# AcceLog_v00.net
KiCad netlist of a schematic drawn in EAGLE
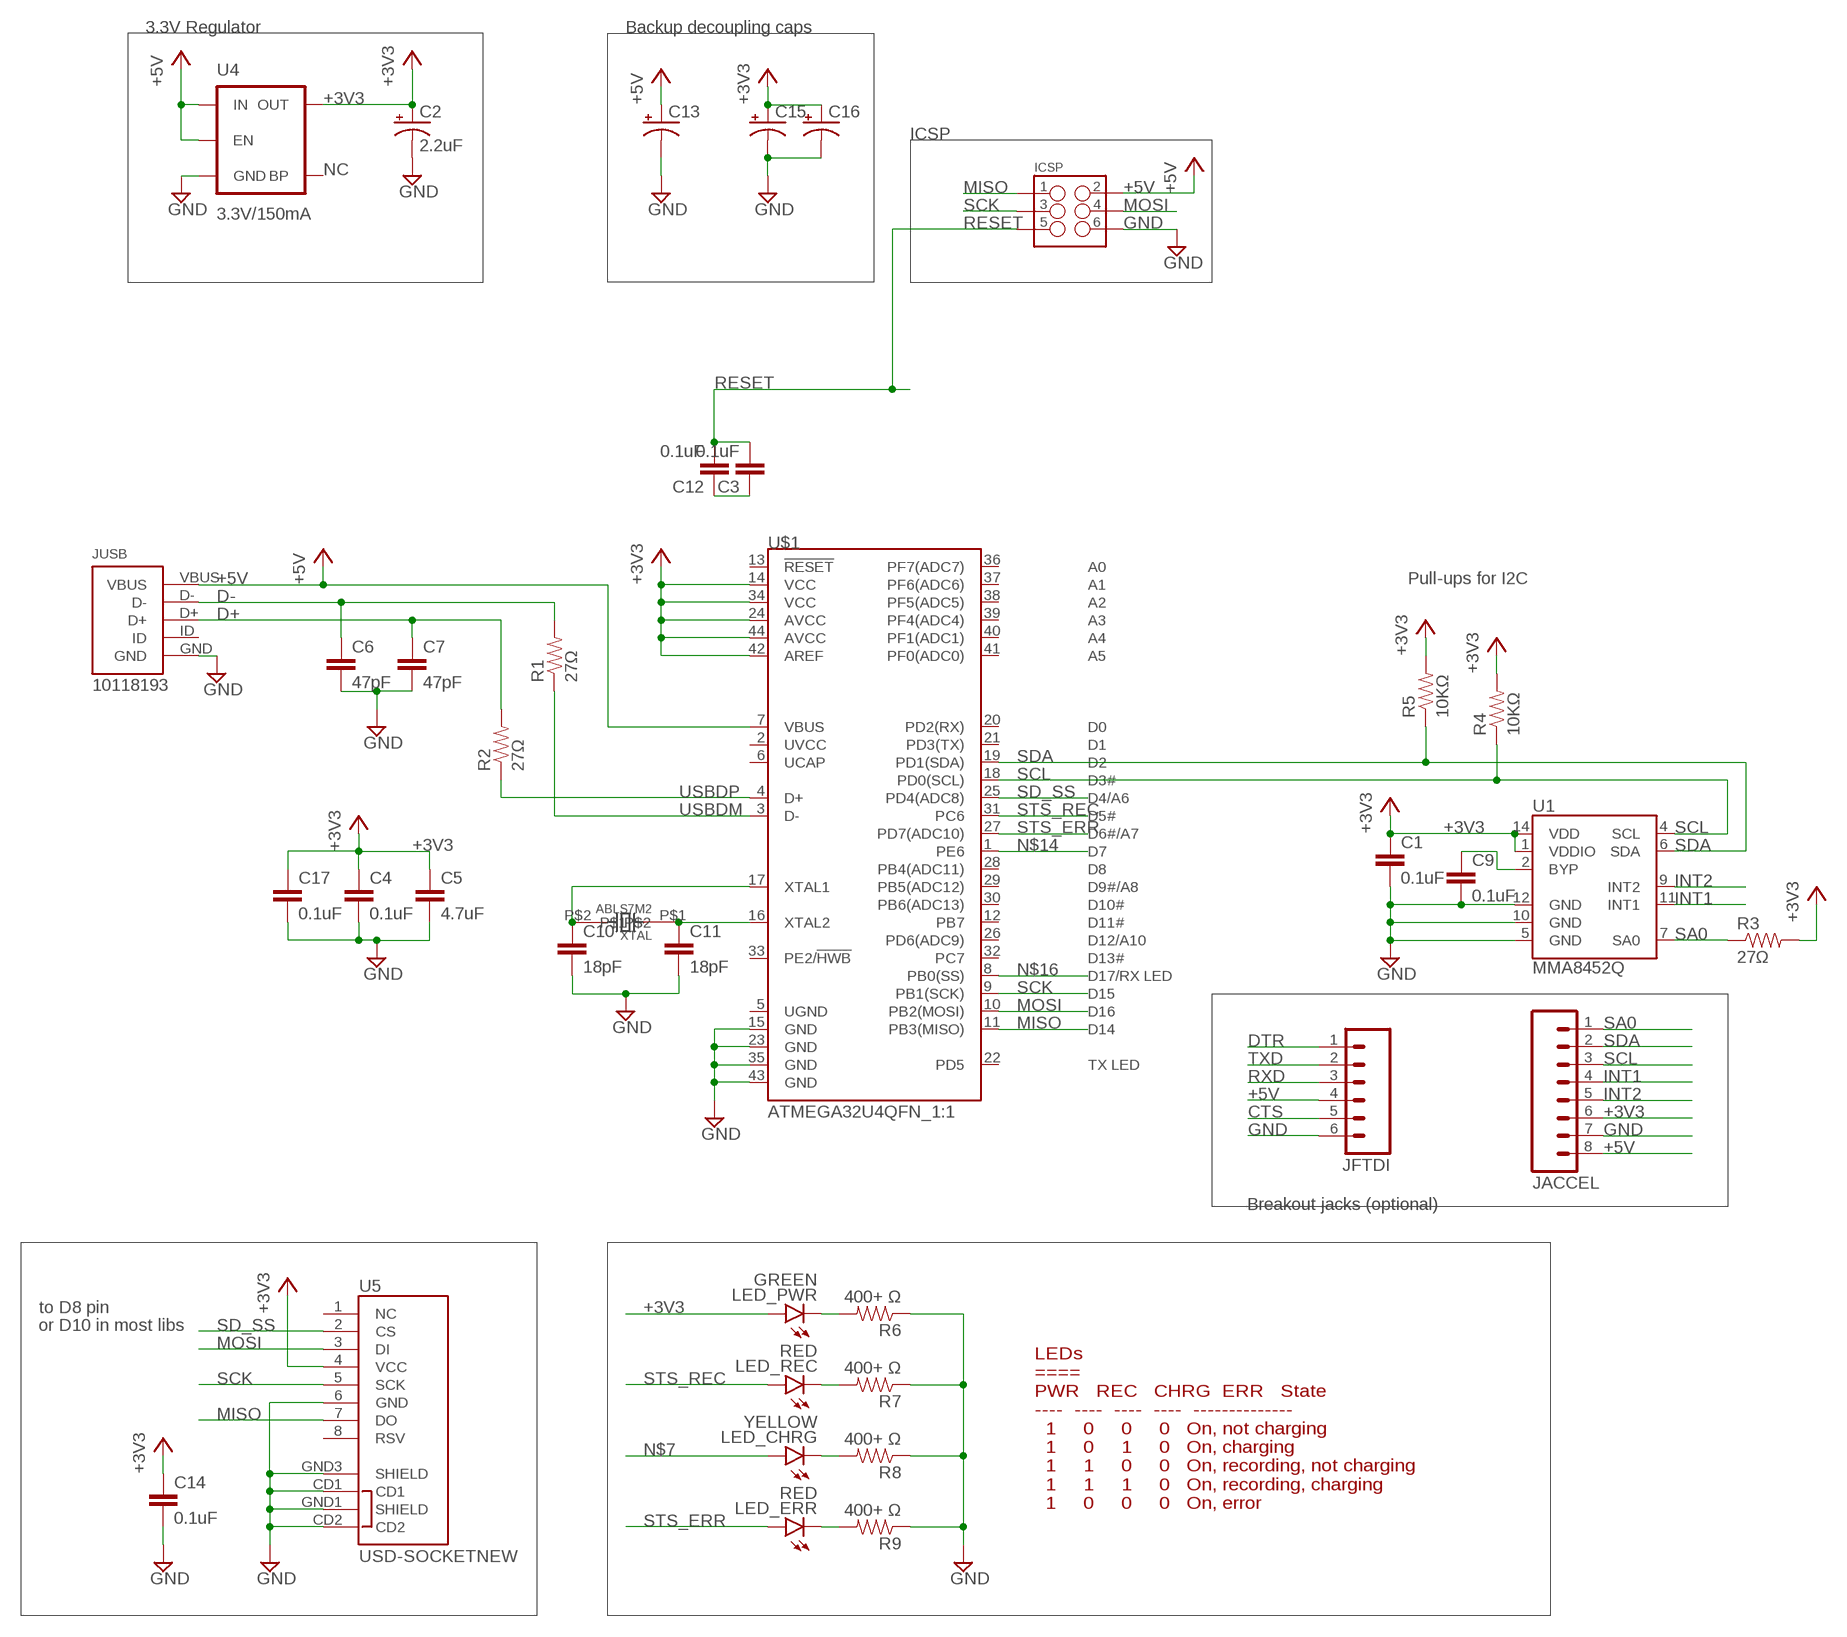
[diagram p0: schematic, sheet 1]

(export (version "E")
  (design (tool "Eeschema 10.0.6"))
  (components
    (comp (ref "C1")
      (value "0.1uF")
      (footprint "eagle-import:0603-CAP")
      (libsource (lib "eagle-import") (part "CAP0603-CAP"))
    )
    (comp (ref "C2")
      (value "2.2uF")
      (footprint "eagle-import:EIA3216")
      (libsource (lib "eagle-import") (part "CAP_POL1206"))
    )
    (comp (ref "C3")
      (value "0.1uF")
      (footprint "eagle-import:0603-CAP")
      (libsource (lib "eagle-import") (part "CAP0603-CAP"))
    )
    (comp (ref "C4")
      (value "0.1uF")
      (footprint "eagle-import:0603-CAP")
      (libsource (lib "eagle-import") (part "CAP0603-CAP"))
    )
    (comp (ref "C5")
      (value "4.7uF")
      (footprint "eagle-import:0603-CAP")
      (libsource (lib "eagle-import") (part "CAP0603-CAP"))
    )
    (comp (ref "C6")
      (value "47pF")
      (footprint "eagle-import:0603-CAP")
      (libsource (lib "eagle-import") (part "CAP0603-CAP"))
    )
    (comp (ref "C7")
      (value "47pF")
      (footprint "eagle-import:0603-CAP")
      (libsource (lib "eagle-import") (part "CAP0603-CAP"))
    )
    (comp (ref "C9")
      (value "0.1uF")
      (footprint "eagle-import:0603-CAP")
      (libsource (lib "eagle-import") (part "CAP0603-CAP"))
    )
    (comp (ref "C10")
      (value "18pF")
      (footprint "eagle-import:0603-CAP")
      (libsource (lib "eagle-import") (part "CAP0603-CAP"))
    )
    (comp (ref "C11")
      (value "18pF")
      (footprint "eagle-import:0603-CAP")
      (libsource (lib "eagle-import") (part "CAP0603-CAP"))
    )
    (comp (ref "C12")
      (value "0.1uF")
      (footprint "eagle-import:0603-CAP")
      (libsource (lib "eagle-import") (part "CAP0603-CAP"))
    )
    (comp (ref "C13")
      (value "CPOL-USE2-5")
      (footprint "eagle-import:E2-5")
      (libsource (lib "eagle-import") (part "CPOL-USE2-5"))
    )
    (comp (ref "C14")
      (value "0.1uF")
      (footprint "eagle-import:0603-CAP")
      (libsource (lib "eagle-import") (part "CAP0603-CAP"))
    )
    (comp (ref "C15")
      (value "CPOL-USE2-5")
      (footprint "eagle-import:E2-5")
      (libsource (lib "eagle-import") (part "CPOL-USE2-5"))
    )
    (comp (ref "C16")
      (value "CPOL-USE2-5")
      (footprint "eagle-import:E2-5")
      (libsource (lib "eagle-import") (part "CPOL-USE2-5"))
    )
    (comp (ref "C17")
      (value "0.1uF")
      (footprint "eagle-import:0603-CAP")
      (libsource (lib "eagle-import") (part "CAP0603-CAP"))
    )
    (comp (ref "ICSP")
      (value "M03X22X3_SILK_MALE_PTH")
      (footprint "eagle-import:2X3")
      (libsource (lib "eagle-import") (part "M03X22X3_SILK_MALE_PTH"))
    )
    (comp (ref "JACCEL")
      (value "M08LOCK")
      (footprint "eagle-import:1X08_LOCK")
      (libsource (lib "eagle-import") (part "M08LOCK"))
    )
    (comp (ref "JFTDI")
      (value "M06LOCK")
      (footprint "eagle-import:1X06_LOCK")
      (libsource (lib "eagle-import") (part "M06LOCK"))
    )
    (comp (ref "JUSB")
      (value "10118193")
      (footprint "eagle-import:10118193")
      (libsource (lib "eagle-import") (part "10118193"))
    )
    (comp (ref "LED_CHRG")
      (value "YELLOW")
      (footprint "eagle-import:LED-0603")
      (libsource (lib "eagle-import") (part "LED0603"))
    )
    (comp (ref "LED_ERR")
      (value "RED")
      (footprint "eagle-import:LED-0603")
      (libsource (lib "eagle-import") (part "LED0603"))
    )
    (comp (ref "LED_PWR")
      (value "GREEN")
      (footprint "eagle-import:LED-0603")
      (libsource (lib "eagle-import") (part "LED0603"))
    )
    (comp (ref "LED_REC")
      (value "RED")
      (footprint "eagle-import:LED-0603")
      (libsource (lib "eagle-import") (part "LED0603"))
    )
    (comp (ref "R1")
      (value "27Ω")
      (footprint "eagle-import:0603-RES")
      (libsource (lib "eagle-import") (part "RESISTOR0603-RES"))
    )
    (comp (ref "R2")
      (value "27Ω")
      (footprint "eagle-import:0603-RES")
      (libsource (lib "eagle-import") (part "RESISTOR0603-RES"))
    )
    (comp (ref "R3")
      (value "27Ω")
      (footprint "eagle-import:0603-RES")
      (libsource (lib "eagle-import") (part "RESISTOR0603-RES"))
    )
    (comp (ref "R4")
      (value "10KΩ")
      (footprint "eagle-import:0603-RES")
      (libsource (lib "eagle-import") (part "RESISTOR0603-RES"))
    )
    (comp (ref "R5")
      (value "10KΩ")
      (footprint "eagle-import:0603-RES")
      (libsource (lib "eagle-import") (part "RESISTOR0603-RES"))
    )
    (comp (ref "R6")
      (value "400+ Ω")
      (footprint "eagle-import:0603-RES")
      (libsource (lib "eagle-import") (part "RESISTOR0603-RES"))
    )
    (comp (ref "R7")
      (value "400+ Ω")
      (footprint "eagle-import:0603-RES")
      (libsource (lib "eagle-import") (part "RESISTOR0603-RES"))
    )
    (comp (ref "R8")
      (value "400+ Ω")
      (footprint "eagle-import:0603-RES")
      (libsource (lib "eagle-import") (part "RESISTOR0603-RES"))
    )
    (comp (ref "R9")
      (value "400+ Ω")
      (footprint "eagle-import:0603-RES")
      (libsource (lib "eagle-import") (part "RESISTOR0603-RES"))
    )
    (comp (ref "U$1")
      (value "ATMEGA32U4QFN_1:1")
      (footprint "eagle-import:QFN-44-NOPAD_1_1")
      (libsource (lib "eagle-import") (part "ATMEGA32U4QFN_1{colon}1"))
    )
    (comp (ref "U1")
      (value "MMA8452Q")
      (footprint "eagle-import:QFN-16_0.5MM")
      (libsource (lib "eagle-import") (part "MMA8452Q"))
    )
    (comp (ref "U4")
      (value "3.3V/150mA")
      (footprint "eagle-import:SOT23-5")
      (libsource (lib "eagle-import") (part "V_REG_MIC52053.3V"))
    )
    (comp (ref "U5")
      (value "USD-SOCKETNEW")
      (footprint "eagle-import:MICRO-SD-SOCKET-PP")
      (libsource (lib "eagle-import") (part "USD-SOCKETNEW"))
    )
    (comp (ref "XTAL")
      (value "ABLS7M2")
      (footprint "eagle-import:ABLS7M2")
      (libsource (lib "eagle-import") (part "ABLS7M2"))
    )
  )
  (nets
    (net (code "1") (name "+3V3") (class "Default")
      (node (ref "C1") (pin "1") (pinfunction "1_1") (pintype "passive"))
      (node (ref "C14") (pin "1") (pinfunction "1_1") (pintype "passive"))
      (node (ref "C15") (pin "+") (pinfunction "+_+") (pintype "passive"))
      (node (ref "C16") (pin "+") (pinfunction "+_+") (pintype "passive"))
      (node (ref "C17") (pin "1") (pinfunction "1_1") (pintype "passive"))
      (node (ref "C2") (pin "A") (pinfunction "+_A") (pintype "passive"))
      (node (ref "C4") (pin "1") (pinfunction "1_1") (pintype "passive"))
      (node (ref "C5") (pin "1") (pinfunction "1_1") (pintype "passive"))
      (node (ref "JACCEL") (pin "6") (pinfunction "6_6") (pintype "passive"))
      (node (ref "LED_PWR") (pin "A") (pinfunction "A_A") (pintype "passive"))
      (node (ref "R3") (pin "2") (pinfunction "2_2") (pintype "passive"))
      (node (ref "R4") (pin "2") (pinfunction "2_2") (pintype "passive"))
      (node (ref "R5") (pin "2") (pinfunction "2_2") (pintype "passive"))
      (node (ref "U$1") (pin "14") (pinfunction "VCC_14") (pintype "bidirectional"))
      (node (ref "U$1") (pin "24") (pinfunction "AVCC_24") (pintype "bidirectional"))
      (node (ref "U$1") (pin "34") (pinfunction "VCC_34") (pintype "bidirectional"))
      (node (ref "U$1") (pin "42") (pinfunction "AREF_42") (pintype "bidirectional"))
      (node (ref "U$1") (pin "44") (pinfunction "AVCC_44") (pintype "bidirectional"))
      (node (ref "U1") (pin "1") (pinfunction "VDDIO_1") (pintype "bidirectional"))
      (node (ref "U1") (pin "14") (pinfunction "VDD_14") (pintype "bidirectional"))
      (node (ref "U4") (pin "5") (pinfunction "OUT_5") (pintype "passive"))
      (node (ref "U5") (pin "4") (pinfunction "VCC_4") (pintype "bidirectional"))
    )
    (net (code "2") (name "+5V") (class "Default")
      (node (ref "C13") (pin "+") (pinfunction "+_+") (pintype "passive"))
      (node (ref "ICSP") (pin "2") (pinfunction "2_2") (pintype "bidirectional"))
      (node (ref "JACCEL") (pin "8") (pinfunction "8_8") (pintype "passive"))
      (node (ref "JFTDI") (pin "4") (pinfunction "4_4") (pintype "passive"))
      (node (ref "JUSB") (pin "VBUS") (pinfunction "VBUS_VBUS") (pintype "bidirectional"))
      (node (ref "U$1") (pin "7") (pinfunction "VBUS_7") (pintype "bidirectional"))
      (node (ref "U4") (pin "1") (pinfunction "IN_1") (pintype "input"))
      (node (ref "U4") (pin "3") (pinfunction "EN_3") (pintype "input"))
    )
    (net (code "3") (name "/CTS") (class "Default")
      (node (ref "JFTDI") (pin "5") (pinfunction "5_5") (pintype "passive"))
    )
    (net (code "4") (name "/D+") (class "Default")
      (node (ref "C7") (pin "1") (pinfunction "1_1") (pintype "passive"))
      (node (ref "JUSB") (pin "D+") (pinfunction "D+_D+") (pintype "bidirectional"))
      (node (ref "R2") (pin "2") (pinfunction "2_2") (pintype "passive"))
    )
    (net (code "5") (name "/D-") (class "Default")
      (node (ref "C6") (pin "1") (pinfunction "1_1") (pintype "passive"))
      (node (ref "JUSB") (pin "D-") (pinfunction "D-_D-") (pintype "bidirectional"))
      (node (ref "R1") (pin "2") (pinfunction "2_2") (pintype "passive"))
    )
    (net (code "6") (name "/DTR") (class "Default")
      (node (ref "C12") (pin "1") (pinfunction "1_1") (pintype "passive"))
      (node (ref "C3") (pin "1") (pinfunction "1_1") (pintype "passive"))
      (node (ref "JFTDI") (pin "1") (pinfunction "1_1") (pintype "passive"))
    )
    (net (code "7") (name "/INT1") (class "Default")
      (node (ref "JACCEL") (pin "4") (pinfunction "4_4") (pintype "passive"))
      (node (ref "U1") (pin "11") (pinfunction "INT1_11") (pintype "bidirectional"))
    )
    (net (code "8") (name "/INT2") (class "Default")
      (node (ref "JACCEL") (pin "5") (pinfunction "5_5") (pintype "passive"))
      (node (ref "U1") (pin "9") (pinfunction "INT2_9") (pintype "bidirectional"))
    )
    (net (code "9") (name "/MISO") (class "Default")
      (node (ref "ICSP") (pin "1") (pinfunction "1_1") (pintype "bidirectional"))
      (node (ref "U$1") (pin "11") (pinfunction "PB3(MISO)_11") (pintype "bidirectional"))
      (node (ref "U5") (pin "7") (pinfunction "DO_7") (pintype "bidirectional"))
    )
    (net (code "10") (name "/MOSI") (class "Default")
      (node (ref "ICSP") (pin "4") (pinfunction "4_4") (pintype "bidirectional"))
      (node (ref "U$1") (pin "10") (pinfunction "PB2(MOSI)_10") (pintype "bidirectional"))
      (node (ref "U5") (pin "3") (pinfunction "DI_3") (pintype "bidirectional"))
    )
    (net (code "11") (name "/N$7") (class "Default")
      (node (ref "LED_CHRG") (pin "A") (pinfunction "A_A") (pintype "passive"))
    )
    (net (code "12") (name "/N$14") (class "Default")
      (node (ref "U$1") (pin "1") (pinfunction "PE6_1") (pintype "bidirectional"))
    )
    (net (code "13") (name "/N$16") (class "Default")
      (node (ref "U$1") (pin "8") (pinfunction "PB0(SS)_8") (pintype "bidirectional"))
    )
    (net (code "14") (name "/RESET") (class "Default")
      (node (ref "C12") (pin "2") (pinfunction "2_2") (pintype "passive"))
      (node (ref "C3") (pin "2") (pinfunction "2_2") (pintype "passive"))
      (node (ref "ICSP") (pin "5") (pinfunction "5_5") (pintype "bidirectional"))
    )
    (net (code "15") (name "/RXD") (class "Default")
      (node (ref "JFTDI") (pin "3") (pinfunction "3_3") (pintype "passive"))
    )
    (net (code "16") (name "/SA0") (class "Default")
      (node (ref "JACCEL") (pin "1") (pinfunction "1_1") (pintype "passive"))
      (node (ref "R3") (pin "1") (pinfunction "1_1") (pintype "passive"))
      (node (ref "U1") (pin "7") (pinfunction "SA0_7") (pintype "bidirectional"))
    )
    (net (code "17") (name "/SCK") (class "Default")
      (node (ref "ICSP") (pin "3") (pinfunction "3_3") (pintype "bidirectional"))
      (node (ref "U$1") (pin "9") (pinfunction "PB1(SCK)_9") (pintype "bidirectional"))
      (node (ref "U5") (pin "5") (pinfunction "SCK_5") (pintype "bidirectional"))
    )
    (net (code "18") (name "/SCL") (class "Default")
      (node (ref "JACCEL") (pin "3") (pinfunction "3_3") (pintype "passive"))
      (node (ref "R4") (pin "1") (pinfunction "1_1") (pintype "passive"))
      (node (ref "U$1") (pin "18") (pinfunction "PD0(SCL)_18") (pintype "bidirectional"))
      (node (ref "U1") (pin "4") (pinfunction "SCL_4") (pintype "bidirectional"))
    )
    (net (code "19") (name "/SDA") (class "Default")
      (node (ref "JACCEL") (pin "2") (pinfunction "2_2") (pintype "passive"))
      (node (ref "R5") (pin "1") (pinfunction "1_1") (pintype "passive"))
      (node (ref "U$1") (pin "19") (pinfunction "PD1(SDA)_19") (pintype "bidirectional"))
      (node (ref "U1") (pin "6") (pinfunction "SDA_6") (pintype "bidirectional"))
    )
    (net (code "20") (name "/SD_SS") (class "Default")
      (node (ref "U$1") (pin "25") (pinfunction "PD4(ADC8)_25") (pintype "bidirectional"))
      (node (ref "U5") (pin "2") (pinfunction "CS_2") (pintype "bidirectional"))
    )
    (net (code "21") (name "/STS_ERR") (class "Default")
      (node (ref "LED_ERR") (pin "A") (pinfunction "A_A") (pintype "passive"))
      (node (ref "U$1") (pin "27") (pinfunction "PD7(ADC10)_27") (pintype "bidirectional"))
    )
    (net (code "22") (name "/STS_REC") (class "Default")
      (node (ref "LED_REC") (pin "A") (pinfunction "A_A") (pintype "passive"))
      (node (ref "U$1") (pin "31") (pinfunction "PC6_31") (pintype "bidirectional"))
    )
    (net (code "23") (name "/TXD") (class "Default")
      (node (ref "JFTDI") (pin "2") (pinfunction "2_2") (pintype "passive"))
    )
    (net (code "24") (name "/USBDM") (class "Default")
      (node (ref "R1") (pin "1") (pinfunction "1_1") (pintype "passive"))
      (node (ref "U$1") (pin "3") (pinfunction "D-_3") (pintype "bidirectional"))
    )
    (net (code "25") (name "/USBDP") (class "Default")
      (node (ref "R2") (pin "1") (pinfunction "1_1") (pintype "passive"))
      (node (ref "U$1") (pin "4") (pinfunction "D+_4") (pintype "bidirectional"))
    )
    (net (code "26") (name "GND") (class "Default")
      (node (ref "C1") (pin "2") (pinfunction "2_2") (pintype "passive"))
      (node (ref "C10") (pin "2") (pinfunction "2_2") (pintype "passive"))
      (node (ref "C11") (pin "2") (pinfunction "2_2") (pintype "passive"))
      (node (ref "C13") (pin "-") (pinfunction "-_-") (pintype "passive"))
      (node (ref "C14") (pin "2") (pinfunction "2_2") (pintype "passive"))
      (node (ref "C15") (pin "-") (pinfunction "-_-") (pintype "passive"))
      (node (ref "C16") (pin "-") (pinfunction "-_-") (pintype "passive"))
      (node (ref "C17") (pin "2") (pinfunction "2_2") (pintype "passive"))
      (node (ref "C2") (pin "C") (pinfunction "-_C") (pintype "passive"))
      (node (ref "C4") (pin "2") (pinfunction "2_2") (pintype "passive"))
      (node (ref "C5") (pin "2") (pinfunction "2_2") (pintype "passive"))
      (node (ref "C6") (pin "2") (pinfunction "2_2") (pintype "passive"))
      (node (ref "C7") (pin "2") (pinfunction "2_2") (pintype "passive"))
      (node (ref "C9") (pin "2") (pinfunction "2_2") (pintype "passive"))
      (node (ref "ICSP") (pin "6") (pinfunction "6_6") (pintype "bidirectional"))
      (node (ref "JACCEL") (pin "7") (pinfunction "7_7") (pintype "passive"))
      (node (ref "JFTDI") (pin "6") (pinfunction "6_6") (pintype "passive"))
      (node (ref "JUSB") (pin "GND") (pinfunction "GND_GND") (pintype "bidirectional"))
      (node (ref "R6") (pin "1") (pinfunction "1_1") (pintype "passive"))
      (node (ref "R7") (pin "1") (pinfunction "1_1") (pintype "passive"))
      (node (ref "R8") (pin "1") (pinfunction "1_1") (pintype "passive"))
      (node (ref "R9") (pin "1") (pinfunction "1_1") (pintype "passive"))
      (node (ref "U$1") (pin "15") (pinfunction "GND_15") (pintype "bidirectional"))
      (node (ref "U$1") (pin "23") (pinfunction "GND_23") (pintype "bidirectional"))
      (node (ref "U$1") (pin "35") (pinfunction "GND_35") (pintype "bidirectional"))
      (node (ref "U$1") (pin "43") (pinfunction "GND_43") (pintype "bidirectional"))
      (node (ref "U1") (pin "10") (pinfunction "GND_10") (pintype "bidirectional"))
      (node (ref "U1") (pin "12") (pinfunction "GND_12") (pintype "bidirectional"))
      (node (ref "U1") (pin "5") (pinfunction "GND_5") (pintype "bidirectional"))
      (node (ref "U4") (pin "2") (pinfunction "GND_2") (pintype "input"))
      (node (ref "U5") (pin "6") (pinfunction "GND_6") (pintype "bidirectional"))
      (node (ref "U5") (pin "CD1") (pinfunction "CD1_CD1") (pintype "bidirectional"))
      (node (ref "U5") (pin "CD2") (pinfunction "CD2_CD2") (pintype "bidirectional"))
      (node (ref "U5") (pin "GND1") (pinfunction "SHIELD_GND1") (pintype "bidirectional"))
      (node (ref "U5") (pin "GND3") (pinfunction "SHIELD_GND3") (pintype "bidirectional"))
    )
    (net (code "27") (name "Net-(LED_CHRG-PadC)") (class "Default")
      (node (ref "LED_CHRG") (pin "C") (pinfunction "C_C") (pintype "passive"))
      (node (ref "R8") (pin "2") (pinfunction "2_2") (pintype "passive"))
    )
    (net (code "28") (name "Net-(LED_ERR-PadC)") (class "Default")
      (node (ref "LED_ERR") (pin "C") (pinfunction "C_C") (pintype "passive"))
      (node (ref "R9") (pin "2") (pinfunction "2_2") (pintype "passive"))
    )
    (net (code "29") (name "Net-(LED_PWR-PadC)") (class "Default")
      (node (ref "LED_PWR") (pin "C") (pinfunction "C_C") (pintype "passive"))
      (node (ref "R6") (pin "2") (pinfunction "2_2") (pintype "passive"))
    )
    (net (code "30") (name "Net-(LED_REC-PadC)") (class "Default")
      (node (ref "LED_REC") (pin "C") (pinfunction "C_C") (pintype "passive"))
      (node (ref "R7") (pin "2") (pinfunction "2_2") (pintype "passive"))
    )
    (net (code "31") (name "Net-(U$1-XTAL1)") (class "Default")
      (node (ref "C10") (pin "1") (pinfunction "1_1") (pintype "passive"))
      (node (ref "U$1") (pin "17") (pinfunction "XTAL1_17") (pintype "bidirectional"))
      (node (ref "XTAL") (pin "P$2") (pinfunction "P$2_P$2") (pintype "bidirectional"))
    )
    (net (code "32") (name "Net-(U$1-XTAL2)") (class "Default")
      (node (ref "C11") (pin "1") (pinfunction "1_1") (pintype "passive"))
      (node (ref "U$1") (pin "16") (pinfunction "XTAL2_16") (pintype "bidirectional"))
      (node (ref "XTAL") (pin "P$1") (pinfunction "P$1_P$1") (pintype "bidirectional"))
    )
    (net (code "33") (name "Net-(U1-BYP)") (class "Default")
      (node (ref "C9") (pin "1") (pinfunction "1_1") (pintype "passive"))
      (node (ref "U1") (pin "2") (pinfunction "BYP_2") (pintype "bidirectional"))
    )
    (net (code "34") (name "unconnected-(JUSB-PadID)") (class "Default")
      (node (ref "JUSB") (pin "ID") (pinfunction "ID_ID") (pintype "bidirectional"))
    )
    (net (code "35") (name "unconnected-(U$1-PB4(ADC11)-Pad28)") (class "Default")
      (node (ref "U$1") (pin "28") (pinfunction "PB4(ADC11)_28") (pintype "bidirectional"))
    )
    (net (code "36") (name "unconnected-(U$1-PB5(ADC12)-Pad29)") (class "Default")
      (node (ref "U$1") (pin "29") (pinfunction "PB5(ADC12)_29") (pintype "bidirectional"))
    )
    (net (code "37") (name "unconnected-(U$1-PB6(ADC13)-Pad30)") (class "Default")
      (node (ref "U$1") (pin "30") (pinfunction "PB6(ADC13)_30") (pintype "bidirectional"))
    )
    (net (code "38") (name "unconnected-(U$1-PB7-Pad12)") (class "Default")
      (node (ref "U$1") (pin "12") (pinfunction "PB7_12") (pintype "bidirectional"))
    )
    (net (code "39") (name "unconnected-(U$1-PC7-Pad32)") (class "Default")
      (node (ref "U$1") (pin "32") (pinfunction "PC7_32") (pintype "bidirectional"))
    )
    (net (code "40") (name "unconnected-(U$1-PD2(RX)-Pad20)") (class "Default")
      (node (ref "U$1") (pin "20") (pinfunction "PD2(RX)_20") (pintype "bidirectional"))
    )
    (net (code "41") (name "unconnected-(U$1-PD3(TX)-Pad21)") (class "Default")
      (node (ref "U$1") (pin "21") (pinfunction "PD3(TX)_21") (pintype "bidirectional"))
    )
    (net (code "42") (name "unconnected-(U$1-PD5-Pad22)") (class "Default")
      (node (ref "U$1") (pin "22") (pinfunction "PD5_22") (pintype "bidirectional"))
    )
    (net (code "43") (name "unconnected-(U$1-PD6(ADC9)-Pad26)") (class "Default")
      (node (ref "U$1") (pin "26") (pinfunction "PD6(ADC9)_26") (pintype "bidirectional"))
    )
    (net (code "44") (name "unconnected-(U$1-PE2{slash}~{HWB}-Pad33)") (class "Default")
      (node (ref "U$1") (pin "33") (pinfunction "PE2/~{HWB}_33") (pintype "bidirectional"))
    )
    (net (code "45") (name "unconnected-(U$1-PF0(ADC0)-Pad41)") (class "Default")
      (node (ref "U$1") (pin "41") (pinfunction "PF0(ADC0)_41") (pintype "bidirectional"))
    )
    (net (code "46") (name "unconnected-(U$1-PF1(ADC1)-Pad40)") (class "Default")
      (node (ref "U$1") (pin "40") (pinfunction "PF1(ADC1)_40") (pintype "bidirectional"))
    )
    (net (code "47") (name "unconnected-(U$1-PF4(ADC4)-Pad39)") (class "Default")
      (node (ref "U$1") (pin "39") (pinfunction "PF4(ADC4)_39") (pintype "bidirectional"))
    )
    (net (code "48") (name "unconnected-(U$1-PF5(ADC5)-Pad38)") (class "Default")
      (node (ref "U$1") (pin "38") (pinfunction "PF5(ADC5)_38") (pintype "bidirectional"))
    )
    (net (code "49") (name "unconnected-(U$1-PF6(ADC6)-Pad37)") (class "Default")
      (node (ref "U$1") (pin "37") (pinfunction "PF6(ADC6)_37") (pintype "bidirectional"))
    )
    (net (code "50") (name "unconnected-(U$1-PF7(ADC7)-Pad36)") (class "Default")
      (node (ref "U$1") (pin "36") (pinfunction "PF7(ADC7)_36") (pintype "bidirectional"))
    )
    (net (code "51") (name "unconnected-(U$1-UCAP-Pad6)") (class "Default")
      (node (ref "U$1") (pin "6") (pinfunction "UCAP_6") (pintype "bidirectional"))
    )
    (net (code "52") (name "unconnected-(U$1-UGND-Pad5)") (class "Default")
      (node (ref "U$1") (pin "5") (pinfunction "UGND_5") (pintype "bidirectional"))
    )
    (net (code "53") (name "unconnected-(U$1-UVCC-Pad2)") (class "Default")
      (node (ref "U$1") (pin "2") (pinfunction "UVCC_2") (pintype "bidirectional"))
    )
    (net (code "54") (name "unconnected-(U$1-~{RESET}-Pad13)") (class "Default")
      (node (ref "U$1") (pin "13") (pinfunction "~{RESET}_13") (pintype "bidirectional"))
    )
    (net (code "55") (name "unconnected-(U4-BP-Pad4)") (class "Default")
      (node (ref "U4") (pin "4") (pinfunction "BP_4") (pintype "input"))
    )
    (net (code "56") (name "unconnected-(U5-NC-Pad1)") (class "Default")
      (node (ref "U5") (pin "1") (pinfunction "NC_1") (pintype "bidirectional"))
    )
    (net (code "57") (name "unconnected-(U5-RSV-Pad8)") (class "Default")
      (node (ref "U5") (pin "8") (pinfunction "RSV_8") (pintype "bidirectional"))
    )
  )
)
